# V_12.net
KiCad netlist of a schematic drawn in Altium Designer
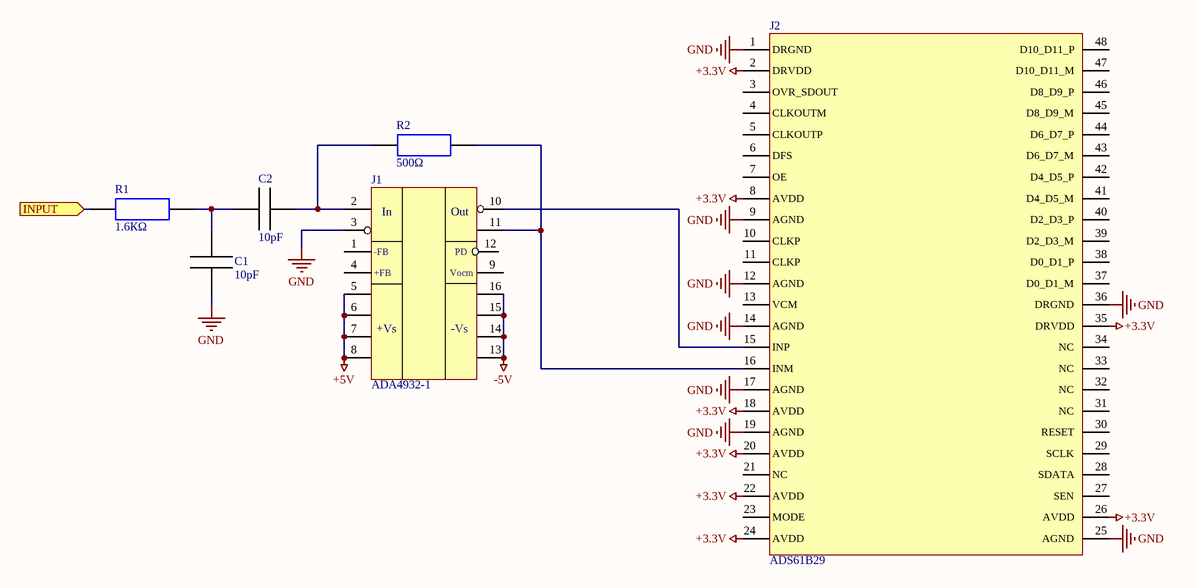
[diagram p0: V_12.SchDoc]

(export (version "E")
  (design (tool "Eeschema 10.0.6"))
  (components
    (comp (ref "C1") (value "10pF") (footprint "1206") (libsource (lib "V_12") (part "C")))
    (comp (ref "C2") (value "10pF") (footprint "1206") (libsource (lib "V_12") (part "C")))
    (comp (ref "J1") (value "ADA4932-1") (footprint "LFCSP_WQ") (libsource (lib "V_12") (part "ADA4932-1")))
    (comp (ref "J2") (value "ADS61B29") (footprint "VQFN") (libsource (lib "V_12") (part "ADS61B29")))
    (comp (ref "R1") (value "1.6КΩ") (footprint "1206") (libsource (lib "V_12") (part "R")))
    (comp (ref "R2") (value "500Ω") (footprint "1206") (libsource (lib "V_12") (part "R")))
  )
  (nets
    (net (code "1") (name "+3.3V") (class "Default")
      (node (ref "J2") (pin "18") (pinfunction "AVDD_18") (pintype "passive"))
      (node (ref "J2") (pin "2") (pinfunction "DRVDD_2") (pintype "passive"))
      (node (ref "J2") (pin "20") (pinfunction "AVDD_20") (pintype "passive"))
      (node (ref "J2") (pin "22") (pinfunction "AVDD_22") (pintype "passive"))
      (node (ref "J2") (pin "24") (pinfunction "AVDD_24") (pintype "passive"))
      (node (ref "J2") (pin "26") (pinfunction "AVDD_26") (pintype "passive"))
      (node (ref "J2") (pin "35") (pinfunction "DRVDD_35") (pintype "passive"))
      (node (ref "J2") (pin "8") (pinfunction "AVDD_8") (pintype "passive"))
    )
    (net (code "2") (name "+5V") (class "Default")
      (node (ref "J1") (pin "5") (pinfunction "+Vs_5") (pintype "passive"))
      (node (ref "J1") (pin "6") (pinfunction "+Vs_6") (pintype "passive"))
      (node (ref "J1") (pin "7") (pinfunction "+Vs_7") (pintype "passive"))
      (node (ref "J1") (pin "8") (pinfunction "+Vs_8") (pintype "passive"))
    )
    (net (code "3") (name "-5V") (class "Default")
      (node (ref "J1") (pin "13") (pinfunction "-Vs_13") (pintype "passive"))
      (node (ref "J1") (pin "14") (pinfunction "-Vs_14") (pintype "passive"))
      (node (ref "J1") (pin "15") (pinfunction "-Vs_15") (pintype "passive"))
      (node (ref "J1") (pin "16") (pinfunction "-Vs_16") (pintype "passive"))
    )
    (net (code "4") (name "/INPUT") (class "Default")
      (node (ref "R1") (pin "1") (pinfunction "1_1") (pintype "passive"))
    )
    (net (code "5") (name "GND") (class "Default")
      (node (ref "C1") (pin "1") (pinfunction "1_1") (pintype "passive"))
      (node (ref "J1") (pin "3") (pinfunction "-IN_3") (pintype "passive"))
      (node (ref "J2") (pin "1") (pinfunction "DRGND_1") (pintype "passive"))
      (node (ref "J2") (pin "12") (pinfunction "AGND_12") (pintype "passive"))
      (node (ref "J2") (pin "14") (pinfunction "AGND_14") (pintype "passive"))
      (node (ref "J2") (pin "17") (pinfunction "AGND_17") (pintype "passive"))
      (node (ref "J2") (pin "19") (pinfunction "AGND_19") (pintype "passive"))
      (node (ref "J2") (pin "25") (pinfunction "AGND_25") (pintype "passive"))
      (node (ref "J2") (pin "36") (pinfunction "DRGND_36") (pintype "passive"))
      (node (ref "J2") (pin "9") (pinfunction "AGND_9") (pintype "passive"))
    )
    (net (code "6") (name "Net-(C1-Pad2)") (class "Default")
      (node (ref "C1") (pin "2") (pinfunction "2_2") (pintype "passive"))
      (node (ref "C2") (pin "1") (pinfunction "1_1") (pintype "passive"))
      (node (ref "R1") (pin "2") (pinfunction "2_2") (pintype "passive"))
    )
    (net (code "7") (name "Net-(J1-+IN)") (class "Default")
      (node (ref "C2") (pin "2") (pinfunction "2_2") (pintype "passive"))
      (node (ref "J1") (pin "2") (pinfunction "+IN_2") (pintype "passive"))
      (node (ref "R2") (pin "1") (pinfunction "1_1") (pintype "passive"))
    )
    (net (code "8") (name "Net-(J1-+OUT)") (class "Default")
      (node (ref "J1") (pin "10") (pinfunction "+OUT_10") (pintype "passive"))
      (node (ref "J2") (pin "15") (pinfunction "INP_15") (pintype "passive"))
    )
    (net (code "9") (name "Net-(J1--OUT)") (class "Default")
      (node (ref "J1") (pin "11") (pinfunction "-OUT_11") (pintype "passive"))
      (node (ref "J2") (pin "16") (pinfunction "INM_16") (pintype "passive"))
      (node (ref "R2") (pin "2") (pinfunction "2_2") (pintype "passive"))
    )
    (net (code "10") (name "unconnected-(J1-+FB-Pad4)") (class "Default")
      (node (ref "J1") (pin "4") (pinfunction "+FB_4") (pintype "passive"))
    )
    (net (code "11") (name "unconnected-(J1--FB-Pad1)") (class "Default")
      (node (ref "J1") (pin "1") (pinfunction "-FB_1") (pintype "passive"))
    )
    (net (code "12") (name "unconnected-(J1-PD-Pad12)") (class "Default")
      (node (ref "J1") (pin "12") (pinfunction "PD_12") (pintype "passive"))
    )
    (net (code "13") (name "unconnected-(J1-Vocm-Pad9)") (class "Default")
      (node (ref "J1") (pin "9") (pinfunction "Vocm_9") (pintype "passive"))
    )
    (net (code "14") (name "unconnected-(J2-CLKOUTM-Pad4)") (class "Default")
      (node (ref "J2") (pin "4") (pinfunction "CLKOUTM_4") (pintype "passive"))
    )
    (net (code "15") (name "unconnected-(J2-CLKOUTP-Pad5)") (class "Default")
      (node (ref "J2") (pin "5") (pinfunction "CLKOUTP_5") (pintype "passive"))
    )
    (net (code "16") (name "unconnected-(J2-CLKP-Pad10)") (class "Default")
      (node (ref "J2") (pin "10") (pinfunction "CLKP_10") (pintype "passive"))
    )
    (net (code "17") (name "unconnected-(J2-CLKP-Pad11)") (class "Default")
      (node (ref "J2") (pin "11") (pinfunction "CLKP_11") (pintype "passive"))
    )
    (net (code "18") (name "unconnected-(J2-D0_D1_M-Pad37)") (class "Default")
      (node (ref "J2") (pin "37") (pinfunction "D0_D1_M_37") (pintype "passive"))
    )
    (net (code "19") (name "unconnected-(J2-D0_D1_P-Pad38)") (class "Default")
      (node (ref "J2") (pin "38") (pinfunction "D0_D1_P_38") (pintype "passive"))
    )
    (net (code "20") (name "unconnected-(J2-D2_D3_M-Pad39)") (class "Default")
      (node (ref "J2") (pin "39") (pinfunction "D2_D3_M_39") (pintype "passive"))
    )
    (net (code "21") (name "unconnected-(J2-D2_D3_P-Pad40)") (class "Default")
      (node (ref "J2") (pin "40") (pinfunction "D2_D3_P_40") (pintype "passive"))
    )
    (net (code "22") (name "unconnected-(J2-D4_D5_M-Pad41)") (class "Default")
      (node (ref "J2") (pin "41") (pinfunction "D4_D5_M_41") (pintype "passive"))
    )
    (net (code "23") (name "unconnected-(J2-D4_D5_P-Pad42)") (class "Default")
      (node (ref "J2") (pin "42") (pinfunction "D4_D5_P_42") (pintype "passive"))
    )
    (net (code "24") (name "unconnected-(J2-D6_D7_M-Pad43)") (class "Default")
      (node (ref "J2") (pin "43") (pinfunction "D6_D7_M_43") (pintype "passive"))
    )
    (net (code "25") (name "unconnected-(J2-D6_D7_P-Pad44)") (class "Default")
      (node (ref "J2") (pin "44") (pinfunction "D6_D7_P_44") (pintype "passive"))
    )
    (net (code "26") (name "unconnected-(J2-D8_D9_M-Pad45)") (class "Default")
      (node (ref "J2") (pin "45") (pinfunction "D8_D9_M_45") (pintype "passive"))
    )
    (net (code "27") (name "unconnected-(J2-D8_D9_P-Pad46)") (class "Default")
      (node (ref "J2") (pin "46") (pinfunction "D8_D9_P_46") (pintype "passive"))
    )
    (net (code "28") (name "unconnected-(J2-D10_D11_M-Pad47)") (class "Default")
      (node (ref "J2") (pin "47") (pinfunction "D10_D11_M_47") (pintype "passive"))
    )
    (net (code "29") (name "unconnected-(J2-D10_D11_P-Pad48)") (class "Default")
      (node (ref "J2") (pin "48") (pinfunction "D10_D11_P_48") (pintype "passive"))
    )
    (net (code "30") (name "unconnected-(J2-DFS-Pad6)") (class "Default")
      (node (ref "J2") (pin "6") (pinfunction "DFS_6") (pintype "passive"))
    )
    (net (code "31") (name "unconnected-(J2-MODE-Pad23)") (class "Default")
      (node (ref "J2") (pin "23") (pinfunction "MODE_23") (pintype "passive"))
    )
    (net (code "32") (name "unconnected-(J2-NC-Pad21)") (class "Default")
      (node (ref "J2") (pin "21") (pinfunction "NC_21") (pintype "passive"))
    )
    (net (code "33") (name "unconnected-(J2-NC-Pad31)") (class "Default")
      (node (ref "J2") (pin "31") (pinfunction "NC_31") (pintype "passive"))
    )
    (net (code "34") (name "unconnected-(J2-NC-Pad32)") (class "Default")
      (node (ref "J2") (pin "32") (pinfunction "NC_32") (pintype "passive"))
    )
    (net (code "35") (name "unconnected-(J2-NC-Pad33)") (class "Default")
      (node (ref "J2") (pin "33") (pinfunction "NC_33") (pintype "passive"))
    )
    (net (code "36") (name "unconnected-(J2-NC-Pad34)") (class "Default")
      (node (ref "J2") (pin "34") (pinfunction "NC_34") (pintype "passive"))
    )
    (net (code "37") (name "unconnected-(J2-OE-Pad7)") (class "Default")
      (node (ref "J2") (pin "7") (pinfunction "OE_7") (pintype "passive"))
    )
    (net (code "38") (name "unconnected-(J2-OVR_SDOUT-Pad3)") (class "Default")
      (node (ref "J2") (pin "3") (pinfunction "OVR_SDOUT_3") (pintype "passive"))
    )
    (net (code "39") (name "unconnected-(J2-RESET-Pad30)") (class "Default")
      (node (ref "J2") (pin "30") (pinfunction "RESET_30") (pintype "passive"))
    )
    (net (code "40") (name "unconnected-(J2-SCLK-Pad29)") (class "Default")
      (node (ref "J2") (pin "29") (pinfunction "SCLK_29") (pintype "passive"))
    )
    (net (code "41") (name "unconnected-(J2-SDATA-Pad28)") (class "Default")
      (node (ref "J2") (pin "28") (pinfunction "SDATA_28") (pintype "passive"))
    )
    (net (code "42") (name "unconnected-(J2-SEN-Pad27)") (class "Default")
      (node (ref "J2") (pin "27") (pinfunction "SEN_27") (pintype "passive"))
    )
    (net (code "43") (name "unconnected-(J2-VCM-Pad13)") (class "Default")
      (node (ref "J2") (pin "13") (pinfunction "VCM_13") (pintype "passive"))
    )
  )
)
